# Sheet1.net
KiCad netlist of a schematic drawn in Altium Designer
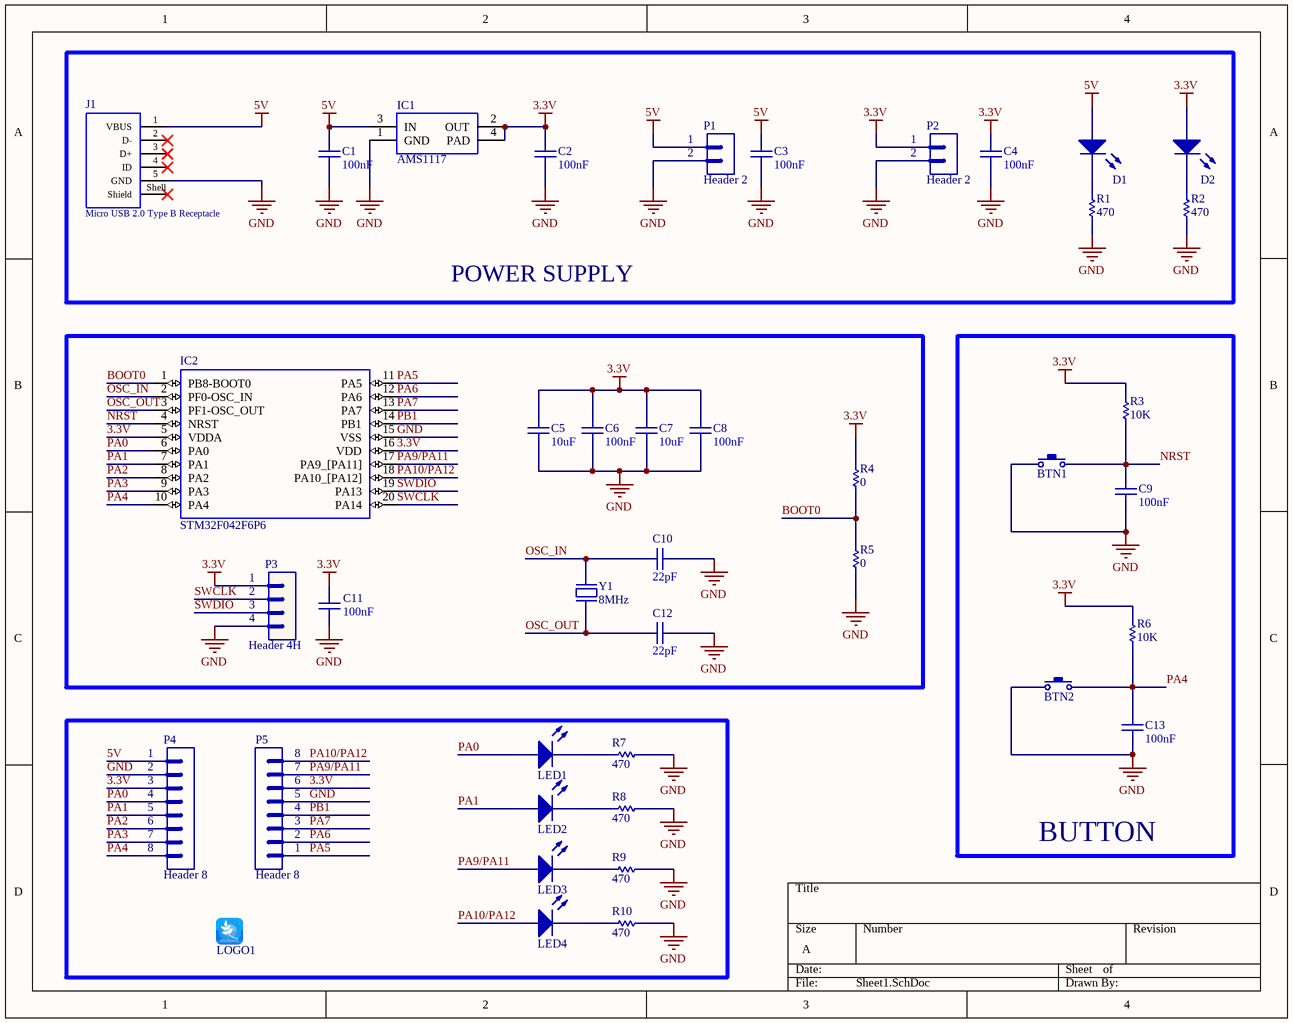
[diagram p0: Sheet1.SchDoc]

(export (version "E")
  (design (tool "Eeschema 10.0.6"))
  (components
    (comp (ref "BTN1")
      (value "Button")
      (footprint "434123050836")
      (libsource (lib "Schlib1") (part "Button"))
    )
    (comp (ref "BTN2")
      (value "Button")
      (footprint "434123050836")
      (libsource (lib "Schlib1") (part "Button"))
    )
    (comp (ref "C1")
      (value "100nF")
      (footprint "CAP-SM-0805")
      (description "Capacitor")
      (fields (field (name "Comment") "Cap Non-Pol SMD"))
      (libsource (lib "Schlib1") (part "Cap Non-Pol SMD"))
    )
    (comp (ref "C2")
      (value "100nF")
      (footprint "CAP-SM-0805")
      (description "Capacitor")
      (fields (field (name "Comment") "Cap Non-Pol SMD"))
      (libsource (lib "Schlib1") (part "Cap Non-Pol SMD"))
    )
    (comp (ref "C3")
      (value "100nF")
      (footprint "CAP-SM-0805")
      (description "Capacitor")
      (fields (field (name "Comment") "Cap Non-Pol SMD"))
      (libsource (lib "Schlib1") (part "Cap Non-Pol SMD"))
    )
    (comp (ref "C4")
      (value "100nF")
      (footprint "CAP-SM-0805")
      (description "Capacitor")
      (fields (field (name "Comment") "Cap Non-Pol SMD"))
      (libsource (lib "Schlib1") (part "Cap Non-Pol SMD"))
    )
    (comp (ref "C5")
      (value "10uF")
      (footprint "CAP-SM-0805")
      (description "Capacitor")
      (fields (field (name "Comment") "Cap Non-Pol SMD"))
      (libsource (lib "Schlib1") (part "Cap Non-Pol SMD"))
    )
    (comp (ref "C6")
      (value "100nF")
      (footprint "CAP-SM-0805")
      (description "Capacitor")
      (fields (field (name "Comment") "Cap Non-Pol SMD"))
      (libsource (lib "Schlib1") (part "Cap Non-Pol SMD"))
    )
    (comp (ref "C7")
      (value "10uF")
      (footprint "CAP-SM-0805")
      (description "Capacitor")
      (fields (field (name "Comment") "Cap Non-Pol SMD"))
      (libsource (lib "Schlib1") (part "Cap Non-Pol SMD"))
    )
    (comp (ref "C8")
      (value "100nF")
      (footprint "CAP-SM-0805")
      (description "Capacitor")
      (fields (field (name "Comment") "Cap Non-Pol SMD"))
      (libsource (lib "Schlib1") (part "Cap Non-Pol SMD"))
    )
    (comp (ref "C9")
      (value "100nF")
      (footprint "CAP-SM-0805")
      (description "Capacitor")
      (fields (field (name "Comment") "Cap Non-Pol SMD"))
      (libsource (lib "Schlib1") (part "Cap Non-Pol SMD"))
    )
    (comp (ref "C10")
      (value "22pF")
      (footprint "CAP-SM-0805")
      (description "Capacitor")
      (fields (field (name "Comment") "Cap Non-Pol SMD"))
      (libsource (lib "Schlib1") (part "Cap Non-Pol SMD"))
    )
    (comp (ref "C11")
      (value "100nF")
      (footprint "CAP-SM-0805")
      (description "Capacitor")
      (fields (field (name "Comment") "Cap Non-Pol SMD"))
      (libsource (lib "Schlib1") (part "Cap Non-Pol SMD"))
    )
    (comp (ref "C12")
      (value "22pF")
      (footprint "CAP-SM-0805")
      (description "Capacitor")
      (fields (field (name "Comment") "Cap Non-Pol SMD"))
      (libsource (lib "Schlib1") (part "Cap Non-Pol SMD"))
    )
    (comp (ref "C13")
      (value "100nF")
      (footprint "CAP-SM-0805")
      (description "Capacitor")
      (fields (field (name "Comment") "Cap Non-Pol SMD"))
      (libsource (lib "Schlib1") (part "Cap Non-Pol SMD"))
    )
    (comp (ref "D1") (value "LED") (footprint "LED_0805_Blue") (libsource (lib "Schlib1") (part "LED")))
    (comp (ref "D2") (value "LED") (footprint "LED_0805_Blue") (libsource (lib "Schlib1") (part "LED")))
    (comp (ref "IC1")
      (value "AMS1117")
      (footprint "SOT223")
      (description "Available in 1.8V, 2.5V, 2.85V, 3.3V, 5V, and  Adjustable Versions")
      (libsource (lib "Schlib1") (part "AMS1117"))
    )
    (comp (ref "IC2")
      (value "STM32F042F6P6")
      (footprint "TSSOP20")
      (description "ARMÂ® CortexÂ®-M0 STM32F0 Microcontroller IC 32-Bit 48MHz 32KB _32K x 8_ FLASH 20-TSSOP")
      (fields (field (name "MF") "STMicroelectronics"))
      (libsource (lib "Schlib1") (part "STM32F042F6P6"))
    )
    (comp (ref "J1")
      (value "Micro USB 2.0 Type B Receptacle")
      (footprint "629105136821")
      (description "Micro USB 2.0 Type B, Receptacle, Horizontal, SMT")
      (fields
        (field (name "MANUFACTURER") "Wurth Elektronik")
        (field (name "MANUFACTURER PART NUMBER") "629105136821")
      )
      (libsource (lib "Schlib1") (part "629105136821"))
    )
    (comp (ref "LED1") (value "LED") (footprint "LED_0805_Blue") (libsource (lib "Board_C22") (part "LED")))
    (comp (ref "LED2") (value "LED") (footprint "LED_0805_Blue") (libsource (lib "Board_C22") (part "LED")))
    (comp (ref "LED3") (value "LED") (footprint "LED_0805_Blue") (libsource (lib "Board_C22") (part "LED")))
    (comp (ref "LED4") (value "LED") (footprint "LED_0805_Blue") (libsource (lib "Board_C22") (part "LED")))
    (comp (ref "LOGO1")
      (value "LOGO PIF")
      (footprint "PIF LOGO BOTTOM OVERLAY")
      (libsource (lib "Schlib1") (part "LOGO PIF"))
    )
    (comp (ref "P1")
      (value "Header 2")
      (footprint "JP2")
      (description "Header, 2-Pin")
      (fields (field (name "PUBLISHER") "Altium Limited"))
      (libsource (lib "Schlib1") (part "Header 2"))
    )
    (comp (ref "P2")
      (value "Header 2")
      (footprint "JP2")
      (description "Header, 2-Pin")
      (fields (field (name "PUBLISHER") "Altium Limited"))
      (libsource (lib "Schlib1") (part "Header 2"))
    )
    (comp (ref "P3")
      (value "Header 4H")
      (footprint "JP4H")
      (description "Header, 4-Pin, Right Angle")
      (fields (field (name "PUBLISHER") "Altium Limited"))
      (libsource (lib "Schlib1") (part "Header 4H"))
    )
    (comp (ref "P4")
      (value "Header 8")
      (footprint "JP8")
      (description "Header, 8-Pin")
      (fields (field (name "PUBLISHER") "Altium Limited"))
      (libsource (lib "") (part "Header 8_1"))
    )
    (comp (ref "P5")
      (value "Header 8")
      (footprint "JP8")
      (description "Header, 8-Pin")
      (fields (field (name "PUBLISHER") "Altium Limited"))
      (libsource (lib "Schlib1") (part "Header 8"))
    )
    (comp (ref "R1")
      (value "470")
      (footprint "RES-SM-0805")
      (fields (field (name "Comment") "Resistor 1/4W"))
      (libsource (lib "Schlib1") (part "RES"))
    )
    (comp (ref "R2")
      (value "470")
      (footprint "RES-SM-0805")
      (fields (field (name "Comment") "Resistor 1/4W"))
      (libsource (lib "Schlib1") (part "RES"))
    )
    (comp (ref "R3")
      (value "10K")
      (footprint "RES-SM-0805")
      (fields (field (name "Comment") "Resistor 1/4W"))
      (libsource (lib "Schlib1") (part "RES"))
    )
    (comp (ref "R4")
      (value "0")
      (footprint "RES-SM-0805")
      (fields (field (name "Comment") "Resistor 1/4W"))
      (libsource (lib "Schlib1") (part "RES"))
    )
    (comp (ref "R5")
      (value "0")
      (footprint "RES-SM-0805")
      (fields (field (name "Comment") "Resistor 1/4W"))
      (libsource (lib "Schlib1") (part "RES"))
    )
    (comp (ref "R6")
      (value "10K")
      (footprint "RES-SM-0805")
      (fields (field (name "Comment") "Resistor 1/4W"))
      (libsource (lib "Schlib1") (part "RES"))
    )
    (comp (ref "R7")
      (value "470")
      (footprint "RES-SM-0805")
      (fields (field (name "Comment") "Resistor 1/4W"))
      (libsource (lib "Schlib1") (part "RES"))
    )
    (comp (ref "R8")
      (value "470")
      (footprint "RES-SM-0805")
      (fields (field (name "Comment") "Resistor 1/4W"))
      (libsource (lib "Schlib1") (part "RES"))
    )
    (comp (ref "R9")
      (value "470")
      (footprint "RES-SM-0805")
      (fields (field (name "Comment") "Resistor 1/4W"))
      (libsource (lib "Schlib1") (part "RES"))
    )
    (comp (ref "R10")
      (value "470")
      (footprint "RES-SM-0805")
      (fields (field (name "Comment") "Resistor 1/4W"))
      (libsource (lib "Schlib1") (part "RES"))
    )
    (comp (ref "Y1")
      (value "8MHz")
      (footprint "XTAL")
      (description "Crystal For all Crystal 2pin")
      (libsource (lib "Schlib1") (part "XTAL"))
    )
  )
  (nets
    (net (code "1") (name "/BOOT0") (class "Default")
      (node (ref "IC2") (pin "1") (pinfunction "PB8-BOOT0_1") (pintype "bidirectional"))
      (node (ref "R4") (pin "1") (pintype "passive"))
      (node (ref "R5") (pin "2") (pintype "passive"))
    )
    (net (code "2") (name "/NRST") (class "Default")
      (node (ref "BTN1") (pin "2") (pintype "passive"))
      (node (ref "C9") (pin "2") (pinfunction "2_2") (pintype "passive"))
      (node (ref "IC2") (pin "4") (pinfunction "NRST_4") (pintype "bidirectional"))
      (node (ref "R3") (pin "1") (pintype "passive"))
    )
    (net (code "3") (name "/OSC_IN") (class "Default")
      (node (ref "C10") (pin "1") (pinfunction "1_1") (pintype "passive"))
      (node (ref "IC2") (pin "2") (pinfunction "PF0-OSC_IN_2") (pintype "bidirectional"))
      (node (ref "Y1") (pin "2") (pinfunction "2_2") (pintype "passive"))
    )
    (net (code "4") (name "/OSC_OUT") (class "Default")
      (node (ref "C12") (pin "2") (pinfunction "2_2") (pintype "passive"))
      (node (ref "IC2") (pin "3") (pinfunction "PF1-OSC_OUT_3") (pintype "bidirectional"))
      (node (ref "Y1") (pin "1") (pinfunction "1_1") (pintype "passive"))
    )
    (net (code "5") (name "/PA0") (class "Default")
      (node (ref "IC2") (pin "6") (pinfunction "PA0_6") (pintype "bidirectional"))
      (node (ref "LED1") (pin "1") (pinfunction "A_1") (pintype "passive"))
      (node (ref "P4") (pin "4") (pinfunction "4_4") (pintype "passive"))
    )
    (net (code "6") (name "/PA1") (class "Default")
      (node (ref "IC2") (pin "7") (pinfunction "PA1_7") (pintype "bidirectional"))
      (node (ref "LED2") (pin "1") (pinfunction "A_1") (pintype "passive"))
      (node (ref "P4") (pin "5") (pinfunction "5_5") (pintype "passive"))
    )
    (net (code "7") (name "/PA2") (class "Default")
      (node (ref "IC2") (pin "8") (pinfunction "PA2_8") (pintype "bidirectional"))
      (node (ref "P4") (pin "6") (pinfunction "6_6") (pintype "passive"))
    )
    (net (code "8") (name "/PA3") (class "Default")
      (node (ref "IC2") (pin "9") (pinfunction "PA3_9") (pintype "bidirectional"))
      (node (ref "P4") (pin "7") (pinfunction "7_7") (pintype "passive"))
    )
    (net (code "9") (name "/PA4") (class "Default")
      (node (ref "BTN2") (pin "2") (pintype "passive"))
      (node (ref "C13") (pin "2") (pinfunction "2_2") (pintype "passive"))
      (node (ref "IC2") (pin "10") (pinfunction "PA4_10") (pintype "bidirectional"))
      (node (ref "P4") (pin "8") (pinfunction "8_8") (pintype "passive"))
      (node (ref "R6") (pin "1") (pintype "passive"))
    )
    (net (code "10") (name "/PA5") (class "Default")
      (node (ref "IC2") (pin "11") (pinfunction "PA5_11") (pintype "bidirectional"))
      (node (ref "P5") (pin "1") (pinfunction "1_1") (pintype "passive"))
    )
    (net (code "11") (name "/PA6") (class "Default")
      (node (ref "IC2") (pin "12") (pinfunction "PA6_12") (pintype "bidirectional"))
      (node (ref "P5") (pin "2") (pinfunction "2_2") (pintype "passive"))
    )
    (net (code "12") (name "/PA7") (class "Default")
      (node (ref "IC2") (pin "13") (pinfunction "PA7_13") (pintype "bidirectional"))
      (node (ref "P5") (pin "3") (pinfunction "3_3") (pintype "passive"))
    )
    (net (code "13") (name "/PA9{slash}PA11") (class "Default")
      (node (ref "IC2") (pin "17") (pinfunction "PA9_[PA11]_17") (pintype "bidirectional"))
      (node (ref "LED3") (pin "1") (pinfunction "A_1") (pintype "passive"))
      (node (ref "P5") (pin "7") (pinfunction "7_7") (pintype "passive"))
    )
    (net (code "14") (name "/PA10{slash}PA12") (class "Default")
      (node (ref "IC2") (pin "18") (pinfunction "PA10_[PA12]_18") (pintype "bidirectional"))
      (node (ref "LED4") (pin "1") (pinfunction "A_1") (pintype "passive"))
      (node (ref "P5") (pin "8") (pinfunction "8_8") (pintype "passive"))
    )
    (net (code "15") (name "/PB1") (class "Default")
      (node (ref "IC2") (pin "14") (pinfunction "PB1_14") (pintype "bidirectional"))
      (node (ref "P5") (pin "4") (pinfunction "4_4") (pintype "passive"))
    )
    (net (code "16") (name "/SWCLK") (class "Default")
      (node (ref "IC2") (pin "20") (pinfunction "PA14_20") (pintype "bidirectional"))
      (node (ref "P3") (pin "2") (pinfunction "2_2") (pintype "passive"))
    )
    (net (code "17") (name "/SWDIO") (class "Default")
      (node (ref "IC2") (pin "19") (pinfunction "PA13_19") (pintype "bidirectional"))
      (node (ref "P3") (pin "3") (pinfunction "3_3") (pintype "passive"))
    )
    (net (code "18") (name "3.3V") (class "Default")
      (node (ref "C11") (pin "2") (pinfunction "2_2") (pintype "passive"))
      (node (ref "C2") (pin "2") (pinfunction "2_2") (pintype "passive"))
      (node (ref "C4") (pin "2") (pinfunction "2_2") (pintype "passive"))
      (node (ref "C5") (pin "2") (pinfunction "2_2") (pintype "passive"))
      (node (ref "C6") (pin "2") (pinfunction "2_2") (pintype "passive"))
      (node (ref "C7") (pin "2") (pinfunction "2_2") (pintype "passive"))
      (node (ref "C8") (pin "2") (pinfunction "2_2") (pintype "passive"))
      (node (ref "D2") (pin "1") (pinfunction "A_1") (pintype "passive"))
      (node (ref "IC1") (pin "2") (pinfunction "OUT_2") (pintype "passive"))
      (node (ref "IC1") (pin "4") (pinfunction "PAD_4") (pintype "passive"))
      (node (ref "IC2") (pin "16") (pinfunction "VDD_16") (pintype "bidirectional"))
      (node (ref "IC2") (pin "5") (pinfunction "VDDA_5") (pintype "bidirectional"))
      (node (ref "P2") (pin "1") (pinfunction "1_1") (pintype "passive"))
      (node (ref "P3") (pin "1") (pinfunction "1_1") (pintype "passive"))
      (node (ref "P4") (pin "3") (pinfunction "3_3") (pintype "passive"))
      (node (ref "P5") (pin "6") (pinfunction "6_6") (pintype "passive"))
      (node (ref "R3") (pin "2") (pintype "passive"))
      (node (ref "R4") (pin "2") (pintype "passive"))
      (node (ref "R6") (pin "2") (pintype "passive"))
    )
    (net (code "19") (name "5V") (class "Default")
      (node (ref "C1") (pin "2") (pinfunction "2_2") (pintype "passive"))
      (node (ref "C3") (pin "2") (pinfunction "2_2") (pintype "passive"))
      (node (ref "D1") (pin "1") (pinfunction "A_1") (pintype "passive"))
      (node (ref "IC1") (pin "3") (pinfunction "IN_3") (pintype "passive"))
      (node (ref "J1") (pin "1") (pinfunction "VBUS_1") (pintype "passive"))
      (node (ref "P1") (pin "1") (pinfunction "1_1") (pintype "passive"))
      (node (ref "P4") (pin "1") (pinfunction "1_1") (pintype "passive"))
    )
    (net (code "20") (name "GND") (class "Default")
      (node (ref "BTN1") (pin "1") (pintype "passive"))
      (node (ref "BTN2") (pin "1") (pintype "passive"))
      (node (ref "C1") (pin "1") (pinfunction "1_1") (pintype "passive"))
      (node (ref "C10") (pin "2") (pinfunction "2_2") (pintype "passive"))
      (node (ref "C11") (pin "1") (pinfunction "1_1") (pintype "passive"))
      (node (ref "C12") (pin "1") (pinfunction "1_1") (pintype "passive"))
      (node (ref "C13") (pin "1") (pinfunction "1_1") (pintype "passive"))
      (node (ref "C2") (pin "1") (pinfunction "1_1") (pintype "passive"))
      (node (ref "C3") (pin "1") (pinfunction "1_1") (pintype "passive"))
      (node (ref "C4") (pin "1") (pinfunction "1_1") (pintype "passive"))
      (node (ref "C5") (pin "1") (pinfunction "1_1") (pintype "passive"))
      (node (ref "C6") (pin "1") (pinfunction "1_1") (pintype "passive"))
      (node (ref "C7") (pin "1") (pinfunction "1_1") (pintype "passive"))
      (node (ref "C8") (pin "1") (pinfunction "1_1") (pintype "passive"))
      (node (ref "C9") (pin "1") (pinfunction "1_1") (pintype "passive"))
      (node (ref "IC1") (pin "1") (pinfunction "GND_1") (pintype "passive"))
      (node (ref "IC2") (pin "15") (pinfunction "VSS_15") (pintype "bidirectional"))
      (node (ref "J1") (pin "5") (pinfunction "GND_5") (pintype "passive"))
      (node (ref "P1") (pin "2") (pinfunction "2_2") (pintype "passive"))
      (node (ref "P2") (pin "2") (pinfunction "2_2") (pintype "passive"))
      (node (ref "P3") (pin "4") (pinfunction "4_4") (pintype "passive"))
      (node (ref "P4") (pin "2") (pinfunction "2_2") (pintype "passive"))
      (node (ref "P5") (pin "5") (pinfunction "5_5") (pintype "passive"))
      (node (ref "R1") (pin "1") (pintype "passive"))
      (node (ref "R10") (pin "2") (pintype "passive"))
      (node (ref "R2") (pin "1") (pintype "passive"))
      (node (ref "R5") (pin "1") (pintype "passive"))
      (node (ref "R7") (pin "2") (pintype "passive"))
      (node (ref "R8") (pin "2") (pintype "passive"))
      (node (ref "R9") (pin "2") (pintype "passive"))
    )
    (net (code "21") (name "Net-(D1-K)") (class "Default")
      (node (ref "D1") (pin "2") (pinfunction "K_2") (pintype "passive"))
      (node (ref "R1") (pin "2") (pintype "passive"))
    )
    (net (code "22") (name "Net-(D2-K)") (class "Default")
      (node (ref "D2") (pin "2") (pinfunction "K_2") (pintype "passive"))
      (node (ref "R2") (pin "2") (pintype "passive"))
    )
    (net (code "23") (name "Net-(LED1-K)") (class "Default")
      (node (ref "LED1") (pin "2") (pinfunction "K_2") (pintype "passive"))
      (node (ref "R7") (pin "1") (pintype "passive"))
    )
    (net (code "24") (name "Net-(LED2-K)") (class "Default")
      (node (ref "LED2") (pin "2") (pinfunction "K_2") (pintype "passive"))
      (node (ref "R8") (pin "1") (pintype "passive"))
    )
    (net (code "25") (name "Net-(LED3-K)") (class "Default")
      (node (ref "LED3") (pin "2") (pinfunction "K_2") (pintype "passive"))
      (node (ref "R9") (pin "1") (pintype "passive"))
    )
    (net (code "26") (name "Net-(LED4-K)") (class "Default")
      (node (ref "LED4") (pin "2") (pinfunction "K_2") (pintype "passive"))
      (node (ref "R10") (pin "1") (pintype "passive"))
    )
    (net (code "27") (name "unconnected-(J1-D+-Pad3)") (class "Default")
      (node (ref "J1") (pin "3") (pinfunction "D+_3") (pintype "passive+no_connect"))
    )
    (net (code "28") (name "unconnected-(J1-D--Pad2)") (class "Default")
      (node (ref "J1") (pin "2") (pinfunction "D-_2") (pintype "passive+no_connect"))
    )
    (net (code "29") (name "unconnected-(J1-ID-Pad4)") (class "Default")
      (node (ref "J1") (pin "4") (pinfunction "ID_4") (pintype "passive+no_connect"))
    )
    (net (code "30") (name "unconnected-(J1-Shield-PadShell)") (class "Default")
      (node (ref "J1") (pin "Shell") (pinfunction "Shield_Shell") (pintype "passive+no_connect"))
    )
  )
)
